# POTENCIOMETRO.net
KiCad netlist of a schematic drawn in EAGLE
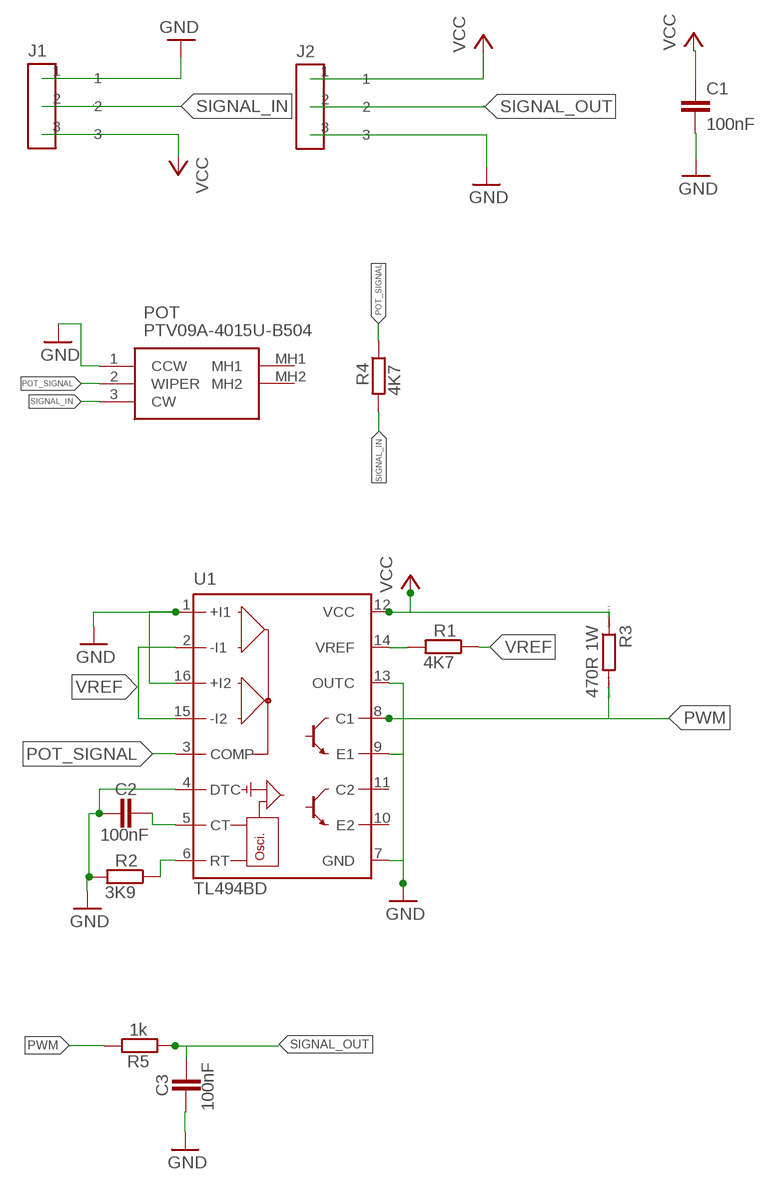
[diagram p0: schematic, sheet 1]

(export (version "E")
  (design (tool "Eeschema 10.0.6"))
  (components
    (comp (ref "C1")
      (value "100nF")
      (footprint "eagle-import:C0805")
      (libsource (lib "eagle-import") (part "C-EUC0805"))
    )
    (comp (ref "C2")
      (value "100nF")
      (footprint "eagle-import:C0805")
      (libsource (lib "eagle-import") (part "C-EUC0805"))
    )
    (comp (ref "C3")
      (value "100nF")
      (footprint "eagle-import:C0805")
      (libsource (lib "eagle-import") (part "C-EUC0805"))
    )
    (comp (ref "J1")
      (value "CONECTOR_MACHO")
      (footprint "eagle-import:MALE")
      (libsource (lib "eagle-import") (part "CONECTOR_MACHO"))
    )
    (comp (ref "J2")
      (value "CONECTOR_FEMEA")
      (footprint "eagle-import:FEMALE")
      (libsource (lib "eagle-import") (part "CONECTOR_FEMEA"))
    )
    (comp (ref "POT")
      (value "PTV09A-4015U-B504")
      (footprint "eagle-import:PTV09A4015UB104")
      (fields (field (name "MOUSER_PART_NUMBER") "652-PTV09A-4015UB504"))
      (libsource (lib "eagle-import") (part "PTV09A-4015U-B504"))
    )
    (comp (ref "R1")
      (value "4K7")
      (footprint "eagle-import:R0805W")
      (libsource (lib "eagle-import") (part "R-EU_R0805W"))
    )
    (comp (ref "R2")
      (value "3K9")
      (footprint "eagle-import:R0805W")
      (libsource (lib "eagle-import") (part "R-EU_R0805W"))
    )
    (comp (ref "R3")
      (value "470R 1W")
      (footprint "eagle-import:R2512")
      (libsource (lib "eagle-import") (part "RR2512"))
    )
    (comp (ref "R4")
      (value "4K7")
      (footprint "eagle-import:R0805W")
      (libsource (lib "eagle-import") (part "R-EU_R0805W"))
    )
    (comp (ref "R5")
      (value "1k")
      (footprint "eagle-import:R0805W")
      (libsource (lib "eagle-import") (part "R-EU_R0805W"))
    )
    (comp (ref "U1")
      (value "TL494BD")
      (footprint "eagle-import:SO16")
      (libsource (lib "eagle-import") (part "TL494DB"))
    )
  )
  (nets
    (net (code "1") (name "GND") (class "Default")
      (node (ref "C1") (pin "2") (pinfunction "2_2") (pintype "passive"))
      (node (ref "C2") (pin "1") (pinfunction "1_1") (pintype "passive"))
      (node (ref "C3") (pin "1") (pinfunction "1_1") (pintype "passive"))
      (node (ref "J1") (pin "1") (pinfunction "1_1") (pintype "bidirectional"))
      (node (ref "J2") (pin "3") (pinfunction "3_3") (pintype "bidirectional"))
      (node (ref "POT") (pin "1") (pinfunction "CCW_1") (pintype "bidirectional"))
      (node (ref "R2") (pin "2") (pinfunction "2_2") (pintype "passive"))
      (node (ref "U1") (pin "1") (pinfunction "+I1_1") (pintype "input"))
      (node (ref "U1") (pin "13") (pinfunction "OUTC_13") (pintype "output"))
      (node (ref "U1") (pin "16") (pinfunction "+I2_16") (pintype "input"))
      (node (ref "U1") (pin "4") (pinfunction "DTC_4") (pintype "input"))
      (node (ref "U1") (pin "7") (pinfunction "GND_7") (pintype "power_in"))
      (node (ref "U1") (pin "9") (pinfunction "E1_9") (pintype "passive"))
    )
    (net (code "2") (name "Net-(U1-CT)") (class "Default")
      (node (ref "C2") (pin "2") (pinfunction "2_2") (pintype "passive"))
      (node (ref "U1") (pin "5") (pinfunction "CT_5") (pintype "input"))
    )
    (net (code "3") (name "Net-(U1-RT)") (class "Default")
      (node (ref "R2") (pin "1") (pinfunction "1_1") (pintype "passive"))
      (node (ref "U1") (pin "6") (pinfunction "RT_6") (pintype "input"))
    )
    (net (code "4") (name "Net-(U1-VREF)") (class "Default")
      (node (ref "R1") (pin "2") (pinfunction "2_2") (pintype "passive"))
      (node (ref "U1") (pin "14") (pinfunction "VREF_14") (pintype "input"))
    )
    (net (code "5") (name "POT_SIGNAL") (class "Default")
      (node (ref "POT") (pin "2") (pinfunction "WIPER_2") (pintype "bidirectional"))
      (node (ref "R4") (pin "1") (pinfunction "1_1") (pintype "passive"))
      (node (ref "U1") (pin "3") (pinfunction "COMP_3") (pintype "passive"))
    )
    (net (code "6") (name "PWM") (class "Default")
      (node (ref "R3") (pin "2") (pinfunction "2_2") (pintype "passive"))
      (node (ref "R5") (pin "1") (pinfunction "1_1") (pintype "passive"))
      (node (ref "U1") (pin "8") (pinfunction "C1_8") (pintype "passive"))
    )
    (net (code "7") (name "SIGNAL_IN") (class "Default")
      (node (ref "J1") (pin "2") (pinfunction "2_2") (pintype "bidirectional"))
      (node (ref "POT") (pin "3") (pinfunction "CW_3") (pintype "bidirectional"))
      (node (ref "R4") (pin "2") (pinfunction "2_2") (pintype "passive"))
    )
    (net (code "8") (name "SIGNAL_OUT") (class "Default")
      (node (ref "C3") (pin "2") (pinfunction "2_2") (pintype "passive"))
      (node (ref "J2") (pin "2") (pinfunction "2_2") (pintype "bidirectional"))
      (node (ref "R5") (pin "2") (pinfunction "2_2") (pintype "passive"))
    )
    (net (code "9") (name "VCC") (class "Default")
      (node (ref "C1") (pin "1") (pinfunction "1_1") (pintype "passive"))
      (node (ref "J1") (pin "3") (pinfunction "3_3") (pintype "bidirectional"))
      (node (ref "J2") (pin "1") (pinfunction "1_1") (pintype "bidirectional"))
      (node (ref "R3") (pin "1") (pinfunction "1_1") (pintype "passive"))
      (node (ref "U1") (pin "12") (pinfunction "VCC_12") (pintype "power_in"))
    )
    (net (code "10") (name "VREF") (class "Default")
      (node (ref "R1") (pin "1") (pinfunction "1_1") (pintype "passive"))
      (node (ref "U1") (pin "15") (pinfunction "-I2_15") (pintype "input"))
      (node (ref "U1") (pin "2") (pinfunction "-I1_2") (pintype "input"))
    )
    (net (code "11") (name "unconnected-(POT-PadMH1)") (class "Default")
      (node (ref "POT") (pin "MH1") (pinfunction "MH1_MH1") (pintype "bidirectional"))
    )
    (net (code "12") (name "unconnected-(POT-PadMH2)") (class "Default")
      (node (ref "POT") (pin "MH2") (pinfunction "MH2_MH2") (pintype "bidirectional"))
    )
    (net (code "13") (name "unconnected-(U1-C2-Pad11)") (class "Default")
      (node (ref "U1") (pin "11") (pinfunction "C2_11") (pintype "passive"))
    )
    (net (code "14") (name "unconnected-(U1-E2-Pad10)") (class "Default")
      (node (ref "U1") (pin "10") (pinfunction "E2_10") (pintype "passive"))
    )
  )
)
